# xmas_pcb_ornament.net
KiCad netlist of a schematic drawn in EAGLE
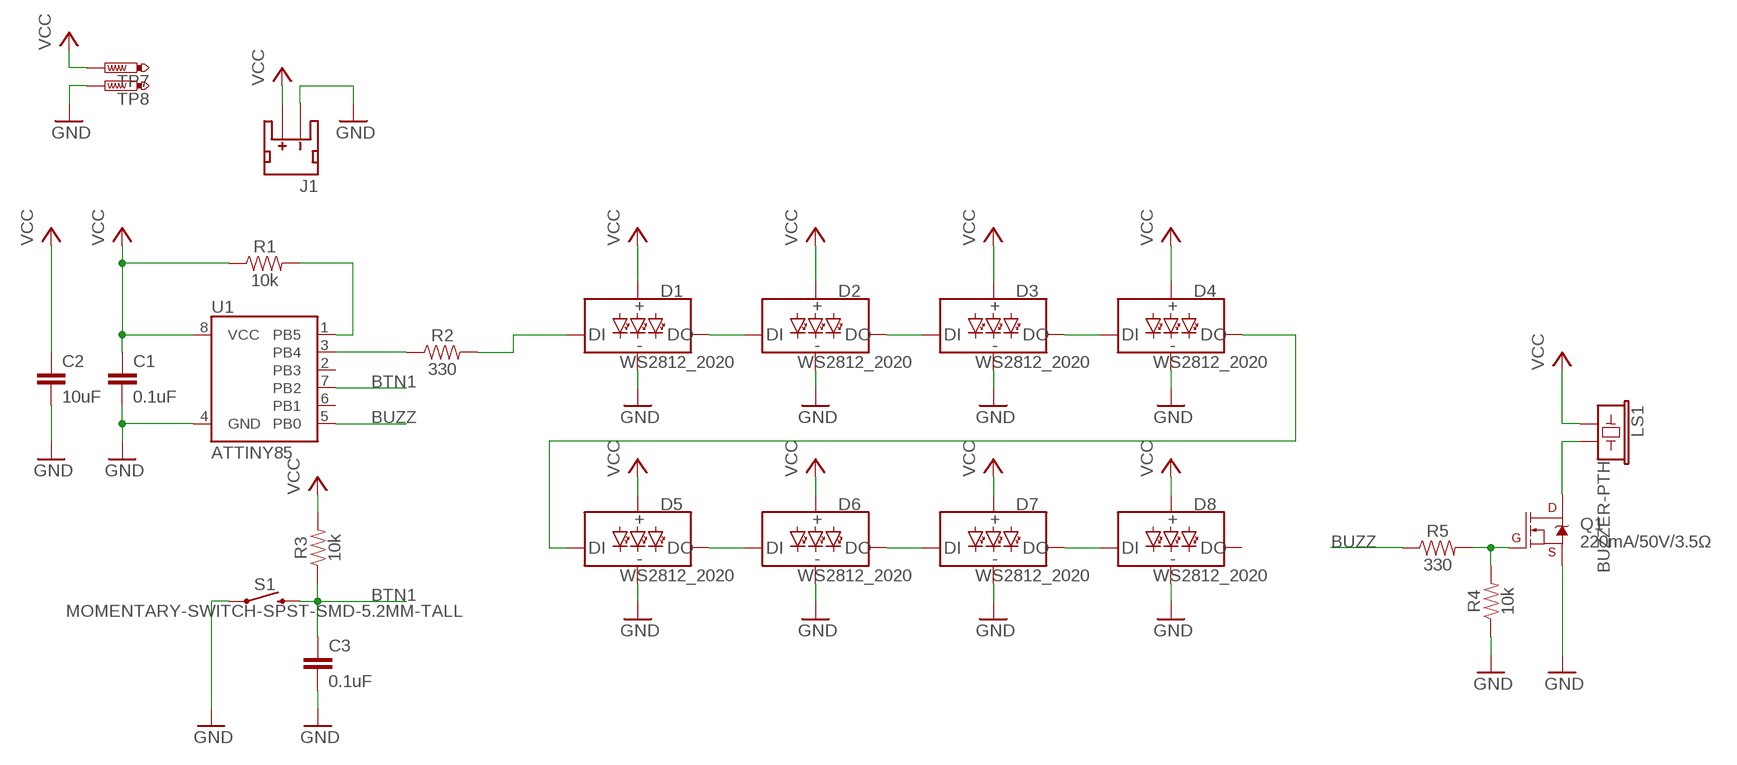
[diagram p0: schematic, sheet 1]

(export (version "E")
  (design (tool "Eeschema 10.0.6"))
  (components
    (comp (ref "C1")
      (value "0.1uF")
      (footprint "eagle-import:0603")
      (libsource (lib "eagle-import") (part "0.1UF-0603-25V-(+80/-20%)"))
    )
    (comp (ref "C2")
      (value "10uF")
      (footprint "eagle-import:1206")
      (libsource (lib "eagle-import") (part "10UF-1206-6.3V-20%"))
    )
    (comp (ref "C3")
      (value "0.1uF")
      (footprint "eagle-import:0603")
      (libsource (lib "eagle-import") (part "0.1UF-0603-25V-(+80/-20%)"))
    )
    (comp (ref "D1")
      (value "WS2812_2020")
      (footprint "eagle-import:WS2812-2020")
      (libsource (lib "eagle-import") (part "WS2812_2020"))
    )
    (comp (ref "D2")
      (value "WS2812_2020")
      (footprint "eagle-import:WS2812-2020")
      (libsource (lib "eagle-import") (part "WS2812_2020"))
    )
    (comp (ref "D3")
      (value "WS2812_2020")
      (footprint "eagle-import:WS2812-2020")
      (libsource (lib "eagle-import") (part "WS2812_2020"))
    )
    (comp (ref "D4")
      (value "WS2812_2020")
      (footprint "eagle-import:WS2812-2020")
      (libsource (lib "eagle-import") (part "WS2812_2020"))
    )
    (comp (ref "D5")
      (value "WS2812_2020")
      (footprint "eagle-import:WS2812-2020")
      (libsource (lib "eagle-import") (part "WS2812_2020"))
    )
    (comp (ref "D6")
      (value "WS2812_2020")
      (footprint "eagle-import:WS2812-2020")
      (libsource (lib "eagle-import") (part "WS2812_2020"))
    )
    (comp (ref "D7")
      (value "WS2812_2020")
      (footprint "eagle-import:WS2812-2020")
      (libsource (lib "eagle-import") (part "WS2812_2020"))
    )
    (comp (ref "D8")
      (value "WS2812_2020")
      (footprint "eagle-import:WS2812-2020")
      (libsource (lib "eagle-import") (part "WS2812_2020"))
    )
    (comp (ref "J1")
      (value "JST_2MM_MALE")
      (footprint "eagle-import:JST-2-SMD")
      (libsource (lib "eagle-import") (part "JST_2MM_MALE"))
    )
    (comp (ref "LS1")
      (value "BUZZER-PTH")
      (footprint "eagle-import:BUZZER-12MM")
      (libsource (lib "eagle-import") (part "BUZZER-PTH"))
    )
    (comp (ref "Q1")
      (value "220mA/50V/3.5Ω")
      (footprint "eagle-import:SOT23-3")
      (libsource (lib "eagle-import") (part "MOSFET-NCH-BSS138"))
    )
    (comp (ref "R1")
      (value "10k")
      (footprint "eagle-import:0603")
      (libsource (lib "eagle-import") (part "10KOHM-0603-1/10W-1%"))
    )
    (comp (ref "R2")
      (value "330")
      (footprint "eagle-import:0603")
      (libsource (lib "eagle-import") (part "330OHM-0603-1/10W-1%"))
    )
    (comp (ref "R3")
      (value "10k")
      (footprint "eagle-import:0603")
      (libsource (lib "eagle-import") (part "10KOHM-0603-1/10W-1%"))
    )
    (comp (ref "R4")
      (value "10k")
      (footprint "eagle-import:0603")
      (libsource (lib "eagle-import") (part "10KOHM-0603-1/10W-1%"))
    )
    (comp (ref "R5")
      (value "330")
      (footprint "eagle-import:0603")
      (libsource (lib "eagle-import") (part "330OHM-0603-1/10W-1%"))
    )
    (comp (ref "S1")
      (value "MOMENTARY-SWITCH-SPST-SMD-5.2MM-TALL")
      (footprint "eagle-import:TACTILE_SWITCH_SMD_5.2MM")
      (libsource (lib "eagle-import") (part "MOMENTARY-SWITCH-SPST-SMD-5.2MM-TALL"))
    )
    (comp (ref "TP7")
      (value "PTR1TP20R")
      (footprint "eagle-import:TP20R")
      (libsource (lib "eagle-import") (part "PTR1TP20R"))
    )
    (comp (ref "TP8")
      (value "PTR1TP20R")
      (footprint "eagle-import:TP20R")
      (libsource (lib "eagle-import") (part "PTR1TP20R"))
    )
    (comp (ref "U1")
      (value "ATTINY85")
      (footprint "eagle-import:ATTINY85")
      (libsource (lib "eagle-import") (part "ATTINY85"))
    )
  )
  (nets
    (net (code "1") (name "/BTN1") (class "Default")
      (node (ref "C3") (pin "1") (pinfunction "1_1") (pintype "passive"))
      (node (ref "R3") (pin "1") (pinfunction "1_1") (pintype "passive"))
      (node (ref "S1") (pin "3") (pinfunction "2_3") (pintype "passive"))
      (node (ref "S1") (pin "4") (pinfunction "2_4") (pintype "passive"))
      (node (ref "U1") (pin "7") (pinfunction "PB2_7") (pintype "bidirectional"))
    )
    (net (code "2") (name "/BUZZ") (class "Default")
      (node (ref "R5") (pin "1") (pinfunction "1_1") (pintype "passive"))
      (node (ref "U1") (pin "5") (pinfunction "PB0_5") (pintype "bidirectional"))
    )
    (net (code "3") (name "GND") (class "Default")
      (node (ref "C1") (pin "2") (pinfunction "2_2") (pintype "passive"))
      (node (ref "C2") (pin "2") (pinfunction "2_2") (pintype "passive"))
      (node (ref "C3") (pin "2") (pinfunction "2_2") (pintype "passive"))
      (node (ref "D1") (pin "GND") (pinfunction "GND_GND") (pintype "bidirectional"))
      (node (ref "D2") (pin "GND") (pinfunction "GND_GND") (pintype "bidirectional"))
      (node (ref "D3") (pin "GND") (pinfunction "GND_GND") (pintype "bidirectional"))
      (node (ref "D4") (pin "GND") (pinfunction "GND_GND") (pintype "bidirectional"))
      (node (ref "D5") (pin "GND") (pinfunction "GND_GND") (pintype "bidirectional"))
      (node (ref "D6") (pin "GND") (pinfunction "GND_GND") (pintype "bidirectional"))
      (node (ref "D7") (pin "GND") (pinfunction "GND_GND") (pintype "bidirectional"))
      (node (ref "D8") (pin "GND") (pinfunction "GND_GND") (pintype "bidirectional"))
      (node (ref "J1") (pin "1") (pinfunction "-_1") (pintype "bidirectional"))
      (node (ref "Q1") (pin "2") (pinfunction "S_2") (pintype "bidirectional"))
      (node (ref "R4") (pin "1") (pinfunction "1_1") (pintype "passive"))
      (node (ref "S1") (pin "1") (pinfunction "1_1") (pintype "passive"))
      (node (ref "S1") (pin "2") (pinfunction "1_2") (pintype "passive"))
      (node (ref "TP8") (pin "TP") (pinfunction "TP_TP") (pintype "input"))
      (node (ref "U1") (pin "4") (pinfunction "GND_4") (pintype "bidirectional"))
    )
    (net (code "4") (name "Net-(D1-PadDI)") (class "Default")
      (node (ref "D1") (pin "DI") (pinfunction "DI_DI") (pintype "bidirectional"))
      (node (ref "R2") (pin "2") (pinfunction "2_2") (pintype "passive"))
    )
    (net (code "5") (name "Net-(D1-PadDO)") (class "Default")
      (node (ref "D1") (pin "DO") (pinfunction "DO_DO") (pintype "bidirectional"))
      (node (ref "D2") (pin "DI") (pinfunction "DI_DI") (pintype "bidirectional"))
    )
    (net (code "6") (name "Net-(D2-PadDO)") (class "Default")
      (node (ref "D2") (pin "DO") (pinfunction "DO_DO") (pintype "bidirectional"))
      (node (ref "D3") (pin "DI") (pinfunction "DI_DI") (pintype "bidirectional"))
    )
    (net (code "7") (name "Net-(D3-PadDO)") (class "Default")
      (node (ref "D3") (pin "DO") (pinfunction "DO_DO") (pintype "bidirectional"))
      (node (ref "D4") (pin "DI") (pinfunction "DI_DI") (pintype "bidirectional"))
    )
    (net (code "8") (name "Net-(D4-PadDO)") (class "Default")
      (node (ref "D4") (pin "DO") (pinfunction "DO_DO") (pintype "bidirectional"))
      (node (ref "D5") (pin "DI") (pinfunction "DI_DI") (pintype "bidirectional"))
    )
    (net (code "9") (name "Net-(D5-PadDO)") (class "Default")
      (node (ref "D5") (pin "DO") (pinfunction "DO_DO") (pintype "bidirectional"))
      (node (ref "D6") (pin "DI") (pinfunction "DI_DI") (pintype "bidirectional"))
    )
    (net (code "10") (name "Net-(D6-PadDO)") (class "Default")
      (node (ref "D6") (pin "DO") (pinfunction "DO_DO") (pintype "bidirectional"))
      (node (ref "D7") (pin "DI") (pinfunction "DI_DI") (pintype "bidirectional"))
    )
    (net (code "11") (name "Net-(D7-PadDO)") (class "Default")
      (node (ref "D7") (pin "DO") (pinfunction "DO_DO") (pintype "bidirectional"))
      (node (ref "D8") (pin "DI") (pinfunction "DI_DI") (pintype "bidirectional"))
    )
    (net (code "12") (name "Net-(LS1-2)") (class "Default")
      (node (ref "LS1") (pin "-") (pinfunction "2_-") (pintype "passive"))
      (node (ref "Q1") (pin "3") (pinfunction "D_3") (pintype "bidirectional"))
    )
    (net (code "13") (name "Net-(Q1-G)") (class "Default")
      (node (ref "Q1") (pin "1") (pinfunction "G_1") (pintype "bidirectional"))
      (node (ref "R4") (pin "2") (pinfunction "2_2") (pintype "passive"))
      (node (ref "R5") (pin "2") (pinfunction "2_2") (pintype "passive"))
    )
    (net (code "14") (name "Net-(U1-PB4)") (class "Default")
      (node (ref "R2") (pin "1") (pinfunction "1_1") (pintype "passive"))
      (node (ref "U1") (pin "3") (pinfunction "PB4_3") (pintype "bidirectional"))
    )
    (net (code "15") (name "Net-(U1-PB5)") (class "Default")
      (node (ref "R1") (pin "2") (pinfunction "2_2") (pintype "passive"))
      (node (ref "U1") (pin "1") (pinfunction "PB5_1") (pintype "bidirectional"))
    )
    (net (code "16") (name "VCC") (class "Default")
      (node (ref "C1") (pin "1") (pinfunction "1_1") (pintype "passive"))
      (node (ref "C2") (pin "1") (pinfunction "1_1") (pintype "passive"))
      (node (ref "D1") (pin "VCC") (pinfunction "VCC_VCC") (pintype "bidirectional"))
      (node (ref "D2") (pin "VCC") (pinfunction "VCC_VCC") (pintype "bidirectional"))
      (node (ref "D3") (pin "VCC") (pinfunction "VCC_VCC") (pintype "bidirectional"))
      (node (ref "D4") (pin "VCC") (pinfunction "VCC_VCC") (pintype "bidirectional"))
      (node (ref "D5") (pin "VCC") (pinfunction "VCC_VCC") (pintype "bidirectional"))
      (node (ref "D6") (pin "VCC") (pinfunction "VCC_VCC") (pintype "bidirectional"))
      (node (ref "D7") (pin "VCC") (pinfunction "VCC_VCC") (pintype "bidirectional"))
      (node (ref "D8") (pin "VCC") (pinfunction "VCC_VCC") (pintype "bidirectional"))
      (node (ref "J1") (pin "2") (pinfunction "+_2") (pintype "bidirectional"))
      (node (ref "LS1") (pin "+") (pinfunction "1_+") (pintype "passive"))
      (node (ref "R1") (pin "1") (pinfunction "1_1") (pintype "passive"))
      (node (ref "R3") (pin "2") (pinfunction "2_2") (pintype "passive"))
      (node (ref "TP7") (pin "TP") (pinfunction "TP_TP") (pintype "input"))
      (node (ref "U1") (pin "8") (pinfunction "VCC_8") (pintype "bidirectional"))
    )
    (net (code "17") (name "unconnected-(D8-PadDO)") (class "Default")
      (node (ref "D8") (pin "DO") (pinfunction "DO_DO") (pintype "bidirectional"))
    )
    (net (code "18") (name "unconnected-(J1-PAD1-PadNC1)") (class "Default")
      (node (ref "J1") (pin "NC1") (pinfunction "PAD1_NC1") (pintype "bidirectional"))
    )
    (net (code "19") (name "unconnected-(J1-PAD2-PadNC2)") (class "Default")
      (node (ref "J1") (pin "NC2") (pinfunction "PAD2_NC2") (pintype "bidirectional"))
    )
    (net (code "20") (name "unconnected-(U1-PB1-Pad6)") (class "Default")
      (node (ref "U1") (pin "6") (pinfunction "PB1_6") (pintype "bidirectional"))
    )
    (net (code "21") (name "unconnected-(U1-PB3-Pad2)") (class "Default")
      (node (ref "U1") (pin "2") (pinfunction "PB3_2") (pintype "bidirectional"))
    )
  )
)
